# Adafruit_AMG8833.net
KiCad netlist of a schematic drawn in EAGLE
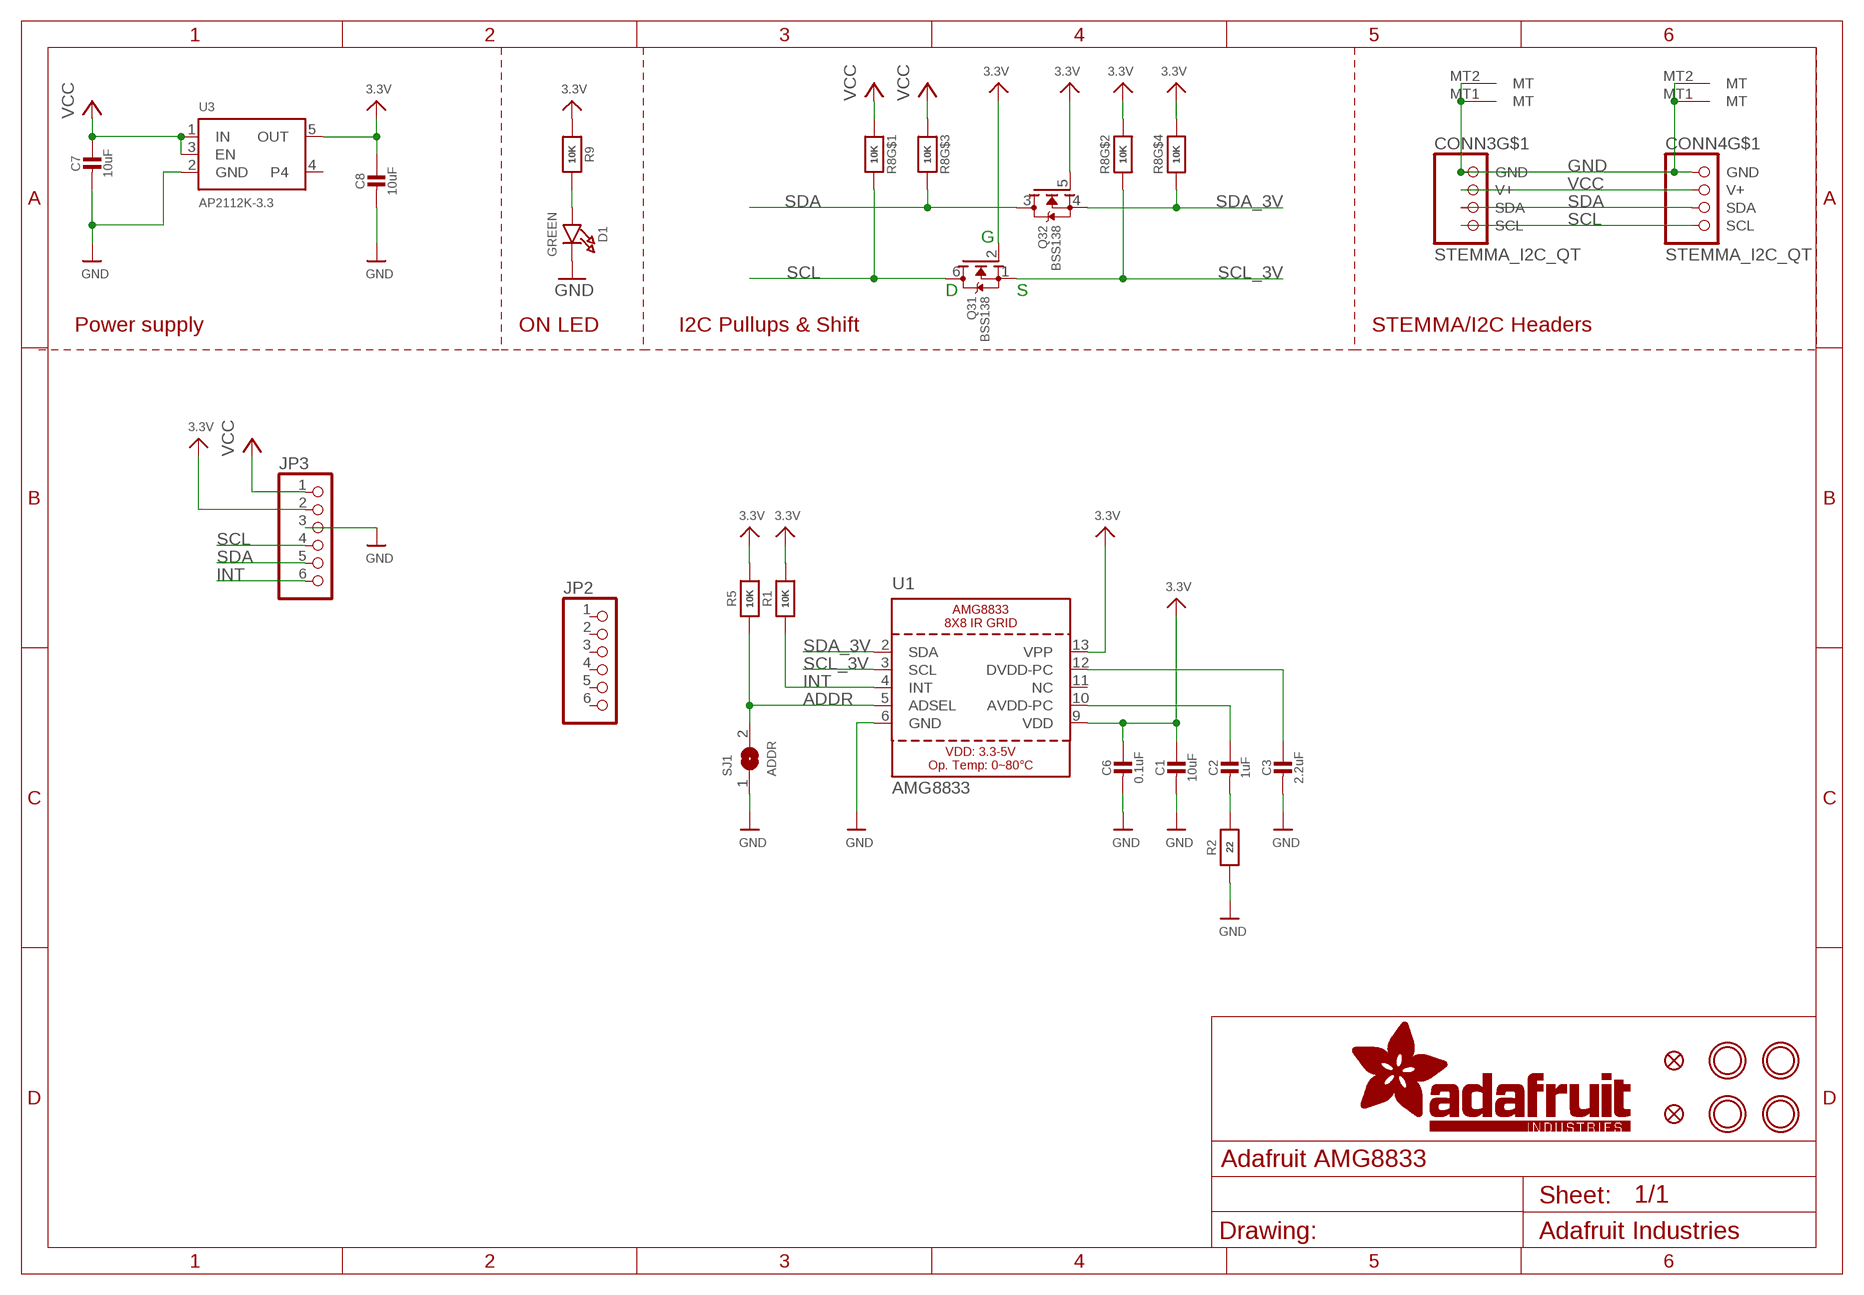
[diagram p0: schematic, sheet 1]

(export (version "E")
  (design (tool "Eeschema 10.0.6"))
  (components
    (comp (ref "C1")
      (value "10uF")
      (footprint "eagle-import:0805-NO")
      (libsource (lib "eagle-import") (part "CAP_CERAMIC0805-NOOUTLINE"))
    )
    (comp (ref "C2")
      (value "1uF")
      (footprint "eagle-import:0603-NO")
      (libsource (lib "eagle-import") (part "CAP_CERAMIC0603_NO"))
    )
    (comp (ref "C3")
      (value "2.2uF")
      (footprint "eagle-import:0805-NO")
      (libsource (lib "eagle-import") (part "CAP_CERAMIC0805-NOOUTLINE"))
    )
    (comp (ref "C6")
      (value "0.1uF")
      (footprint "eagle-import:0603-NO")
      (libsource (lib "eagle-import") (part "CAP_CERAMIC0603_NO"))
    )
    (comp (ref "C7")
      (value "10uF")
      (footprint "eagle-import:0805-NO")
      (libsource (lib "eagle-import") (part "CAP_CERAMIC0805-NOOUTLINE"))
    )
    (comp (ref "C8")
      (value "10uF")
      (footprint "eagle-import:0805-NO")
      (libsource (lib "eagle-import") (part "CAP_CERAMIC0805-NOOUTLINE"))
    )
    (comp (ref "CONN3")
      (value "STEMMA_I2C_QT")
      (footprint "eagle-import:JST_SH4")
      (libsource (lib "eagle-import") (part "STEMMA_I2C_QT"))
    )
    (comp (ref "CONN4")
      (value "STEMMA_I2C_QT")
      (footprint "eagle-import:JST_SH4")
      (libsource (lib "eagle-import") (part "STEMMA_I2C_QT"))
    )
    (comp (ref "D1")
      (value "GREEN")
      (footprint "eagle-import:CHIPLED_0603_NOOUTLINE")
      (libsource (lib "eagle-import") (part "LED0603_NOOUTLINE"))
    )
    (comp (ref "FID1")
      (value "FIDUCIAL_1MM")
      (footprint "eagle-import:FIDUCIAL_1MM")
      (libsource (lib "eagle-import") (part "FIDUCIAL_1MM"))
    )
    (comp (ref "FID4")
      (value "FIDUCIAL_1MM")
      (footprint "eagle-import:FIDUCIAL_1MM")
      (libsource (lib "eagle-import") (part "FIDUCIAL_1MM"))
    )
    (comp (ref "JP2")
      (value "HEADER-1X670MIL")
      (footprint "eagle-import:1X06_ROUND_70")
      (libsource (lib "eagle-import") (part "HEADER-1X670MIL"))
    )
    (comp (ref "JP3")
      (value "HEADER-1X670MIL")
      (footprint "eagle-import:1X06_ROUND_70")
      (libsource (lib "eagle-import") (part "HEADER-1X670MIL"))
    )
    (comp (ref "Q3")
      (value "BSS138")
      (footprint "eagle-import:SOT363")
      (libsource (lib "eagle-import") (part "MOSFET-N_DUAL"))
    )
    (comp (ref "R1")
      (value "10K")
      (footprint "eagle-import:0603-NO")
      (libsource (lib "eagle-import") (part "RESISTOR_0603_NOOUT"))
    )
    (comp (ref "R2")
      (value "22")
      (footprint "eagle-import:0603-NO")
      (libsource (lib "eagle-import") (part "RESISTOR_0603_NOOUT"))
    )
    (comp (ref "R5")
      (value "10K")
      (footprint "eagle-import:0603-NO")
      (libsource (lib "eagle-import") (part "RESISTOR_0603_NOOUT"))
    )
    (comp (ref "R8")
      (value "10K")
      (footprint "eagle-import:RESPACK_4X0603")
      (libsource (lib "eagle-import") (part "RESISTOR_4PACK"))
    )
    (comp (ref "R9")
      (value "10K")
      (footprint "eagle-import:0603-NO")
      (libsource (lib "eagle-import") (part "RESISTOR_0603_NOOUT"))
    )
    (comp (ref "SJ1")
      (value "ADDR")
      (footprint "eagle-import:SOLDERJUMPER_ARROW_NOPASTE")
      (libsource (lib "eagle-import") (part "SOLDERJUMPER"))
    )
    (comp (ref "U$40")
      (value "MOUNTINGHOLE2.5")
      (footprint "eagle-import:MOUNTINGHOLE_2.5_PLATED")
      (libsource (lib "eagle-import") (part "MOUNTINGHOLE2.5"))
    )
    (comp (ref "U$41")
      (value "MOUNTINGHOLE2.5")
      (footprint "eagle-import:MOUNTINGHOLE_2.5_PLATED")
      (libsource (lib "eagle-import") (part "MOUNTINGHOLE2.5"))
    )
    (comp (ref "U$43")
      (value "MOUNTINGHOLE2.5")
      (footprint "eagle-import:MOUNTINGHOLE_2.5_PLATED")
      (libsource (lib "eagle-import") (part "MOUNTINGHOLE2.5"))
    )
    (comp (ref "U$44")
      (value "MOUNTINGHOLE2.5")
      (footprint "eagle-import:MOUNTINGHOLE_2.5_PLATED")
      (libsource (lib "eagle-import") (part "MOUNTINGHOLE2.5"))
    )
    (comp (ref "U1")
      (value "AMG8833")
      (footprint "eagle-import:AMG8833")
      (libsource (lib "eagle-import") (part "AMG8833"))
    )
    (comp (ref "U3")
      (value "AP2112K-3.3")
      (footprint "eagle-import:SOT23-5")
      (libsource (lib "eagle-import") (part "VREG_SOT23-5"))
    )
  )
  (nets
    (net (code "1") (name "/ADDR") (class "Default")
      (node (ref "R5") (pin "1") (pinfunction "1_1") (pintype "passive"))
      (node (ref "SJ1") (pin "2") (pinfunction "2_2") (pintype "passive"))
      (node (ref "U1") (pin "5") (pinfunction "ADSEL_5") (pintype "input"))
    )
    (net (code "2") (name "/INT") (class "Default")
      (node (ref "JP3") (pin "6") (pinfunction "6_6") (pintype "passive"))
      (node (ref "R1") (pin "1") (pinfunction "1_1") (pintype "passive"))
      (node (ref "U1") (pin "4") (pinfunction "INT_4") (pintype "output"))
    )
    (net (code "3") (name "/SCL") (class "Default")
      (node (ref "CONN3") (pin "4") (pinfunction "SCL_4") (pintype "passive"))
      (node (ref "CONN4") (pin "4") (pinfunction "SCL_4") (pintype "passive"))
      (node (ref "JP3") (pin "4") (pinfunction "4_4") (pintype "passive"))
      (node (ref "Q3") (pin "6") (pinfunction "D_6") (pintype "bidirectional"))
      (node (ref "R8") (pin "8") (pinfunction "2_8") (pintype "passive"))
    )
    (net (code "4") (name "/SCL_3V") (class "Default")
      (node (ref "Q3") (pin "1") (pinfunction "S_1") (pintype "bidirectional"))
      (node (ref "R8") (pin "7") (pinfunction "2_7") (pintype "passive"))
      (node (ref "U1") (pin "3") (pinfunction "SCL_3") (pintype "bidirectional"))
    )
    (net (code "5") (name "/SDA") (class "Default")
      (node (ref "CONN3") (pin "3") (pinfunction "SDA_3") (pintype "passive"))
      (node (ref "CONN4") (pin "3") (pinfunction "SDA_3") (pintype "passive"))
      (node (ref "JP3") (pin "5") (pinfunction "5_5") (pintype "passive"))
      (node (ref "Q3") (pin "3") (pinfunction "D_3") (pintype "bidirectional"))
      (node (ref "R8") (pin "6") (pinfunction "2_6") (pintype "passive"))
    )
    (net (code "6") (name "/SDA_3V") (class "Default")
      (node (ref "Q3") (pin "4") (pinfunction "S_4") (pintype "bidirectional"))
      (node (ref "R8") (pin "5") (pinfunction "2_5") (pintype "passive"))
      (node (ref "U1") (pin "2") (pinfunction "SDA_2") (pintype "bidirectional"))
    )
    (net (code "7") (name "3.3V") (class "Default")
      (node (ref "C1") (pin "1") (pinfunction "1_1") (pintype "passive"))
      (node (ref "C6") (pin "1") (pinfunction "1_1") (pintype "passive"))
      (node (ref "C8") (pin "1") (pinfunction "1_1") (pintype "passive"))
      (node (ref "JP3") (pin "2") (pinfunction "2_2") (pintype "passive"))
      (node (ref "Q3") (pin "2") (pinfunction "G_2") (pintype "bidirectional"))
      (node (ref "Q3") (pin "5") (pinfunction "G_5") (pintype "bidirectional"))
      (node (ref "R1") (pin "2") (pinfunction "2_2") (pintype "passive"))
      (node (ref "R5") (pin "2") (pinfunction "2_2") (pintype "passive"))
      (node (ref "R8") (pin "2") (pinfunction "1_2") (pintype "passive"))
      (node (ref "R8") (pin "4") (pinfunction "1_4") (pintype "passive"))
      (node (ref "R9") (pin "1") (pinfunction "1_1") (pintype "passive"))
      (node (ref "U1") (pin "13") (pinfunction "VPP_13") (pintype "power_in"))
      (node (ref "U1") (pin "9") (pinfunction "VDD_9") (pintype "power_in"))
      (node (ref "U3") (pin "5") (pinfunction "OUT_5") (pintype "power_in"))
    )
    (net (code "8") (name "GND") (class "Default")
      (node (ref "C1") (pin "2") (pinfunction "2_2") (pintype "passive"))
      (node (ref "C3") (pin "2") (pinfunction "2_2") (pintype "passive"))
      (node (ref "C6") (pin "2") (pinfunction "2_2") (pintype "passive"))
      (node (ref "C7") (pin "2") (pinfunction "2_2") (pintype "passive"))
      (node (ref "C8") (pin "2") (pinfunction "2_2") (pintype "passive"))
      (node (ref "CONN3") (pin "1") (pinfunction "GND_1") (pintype "passive"))
      (node (ref "CONN3") (pin "MT1") (pinfunction "MT_MT1") (pintype "bidirectional"))
      (node (ref "CONN3") (pin "MT2") (pinfunction "MT_MT2") (pintype "bidirectional"))
      (node (ref "CONN4") (pin "1") (pinfunction "GND_1") (pintype "passive"))
      (node (ref "CONN4") (pin "MT1") (pinfunction "MT_MT1") (pintype "bidirectional"))
      (node (ref "CONN4") (pin "MT2") (pinfunction "MT_MT2") (pintype "bidirectional"))
      (node (ref "D1") (pin "C") (pinfunction "C_C") (pintype "passive"))
      (node (ref "JP3") (pin "3") (pinfunction "3_3") (pintype "passive"))
      (node (ref "R2") (pin "1") (pinfunction "1_1") (pintype "passive"))
      (node (ref "SJ1") (pin "1") (pinfunction "1_1") (pintype "passive"))
      (node (ref "U1") (pin "6") (pinfunction "GND_6") (pintype "power_in"))
      (node (ref "U3") (pin "2") (pinfunction "GND_2") (pintype "power_in"))
    )
    (net (code "9") (name "Net-(C2-Pad2)") (class "Default")
      (node (ref "C2") (pin "2") (pinfunction "2_2") (pintype "passive"))
      (node (ref "R2") (pin "2") (pinfunction "2_2") (pintype "passive"))
    )
    (net (code "10") (name "Net-(D1-PadA)") (class "Default")
      (node (ref "D1") (pin "A") (pinfunction "A_A") (pintype "passive"))
      (node (ref "R9") (pin "2") (pinfunction "2_2") (pintype "passive"))
    )
    (net (code "11") (name "Net-(U1-AVDD-PC)") (class "Default")
      (node (ref "C2") (pin "1") (pinfunction "1_1") (pintype "passive"))
      (node (ref "U1") (pin "10") (pinfunction "AVDD-PC_10") (pintype "power_in"))
    )
    (net (code "12") (name "Net-(U1-DVDD-PC)") (class "Default")
      (node (ref "C3") (pin "1") (pinfunction "1_1") (pintype "passive"))
      (node (ref "U1") (pin "12") (pinfunction "DVDD-PC_12") (pintype "power_in"))
    )
    (net (code "13") (name "VCC") (class "Default")
      (node (ref "C7") (pin "1") (pinfunction "1_1") (pintype "passive"))
      (node (ref "CONN3") (pin "2") (pinfunction "V+_2") (pintype "passive"))
      (node (ref "CONN4") (pin "2") (pinfunction "V+_2") (pintype "passive"))
      (node (ref "JP3") (pin "1") (pinfunction "1_1") (pintype "passive"))
      (node (ref "R8") (pin "1") (pinfunction "1_1") (pintype "passive"))
      (node (ref "R8") (pin "3") (pinfunction "1_3") (pintype "passive"))
      (node (ref "U3") (pin "1") (pinfunction "IN_1") (pintype "power_in"))
      (node (ref "U3") (pin "3") (pinfunction "EN_3") (pintype "input"))
    )
    (net (code "14") (name "unconnected-(JP2-Pad1)") (class "Default")
      (node (ref "JP2") (pin "1") (pinfunction "1_1") (pintype "passive"))
    )
    (net (code "15") (name "unconnected-(JP2-Pad2)") (class "Default")
      (node (ref "JP2") (pin "2") (pinfunction "2_2") (pintype "passive"))
    )
    (net (code "16") (name "unconnected-(JP2-Pad3)") (class "Default")
      (node (ref "JP2") (pin "3") (pinfunction "3_3") (pintype "passive"))
    )
    (net (code "17") (name "unconnected-(JP2-Pad4)") (class "Default")
      (node (ref "JP2") (pin "4") (pinfunction "4_4") (pintype "passive"))
    )
    (net (code "18") (name "unconnected-(JP2-Pad5)") (class "Default")
      (node (ref "JP2") (pin "5") (pinfunction "5_5") (pintype "passive"))
    )
    (net (code "19") (name "unconnected-(JP2-Pad6)") (class "Default")
      (node (ref "JP2") (pin "6") (pinfunction "6_6") (pintype "passive"))
    )
    (net (code "20") (name "unconnected-(U1-NC-Pad11)") (class "Default")
      (node (ref "U1") (pin "11") (pinfunction "NC_11") (pintype "bidirectional"))
    )
    (net (code "21") (name "unconnected-(U3-P4-Pad4)") (class "Default")
      (node (ref "U3") (pin "4") (pinfunction "P4_4") (pintype "bidirectional"))
    )
  )
)
